# smoke_co_interface.net
KiCad netlist of a schematic drawn in EAGLE
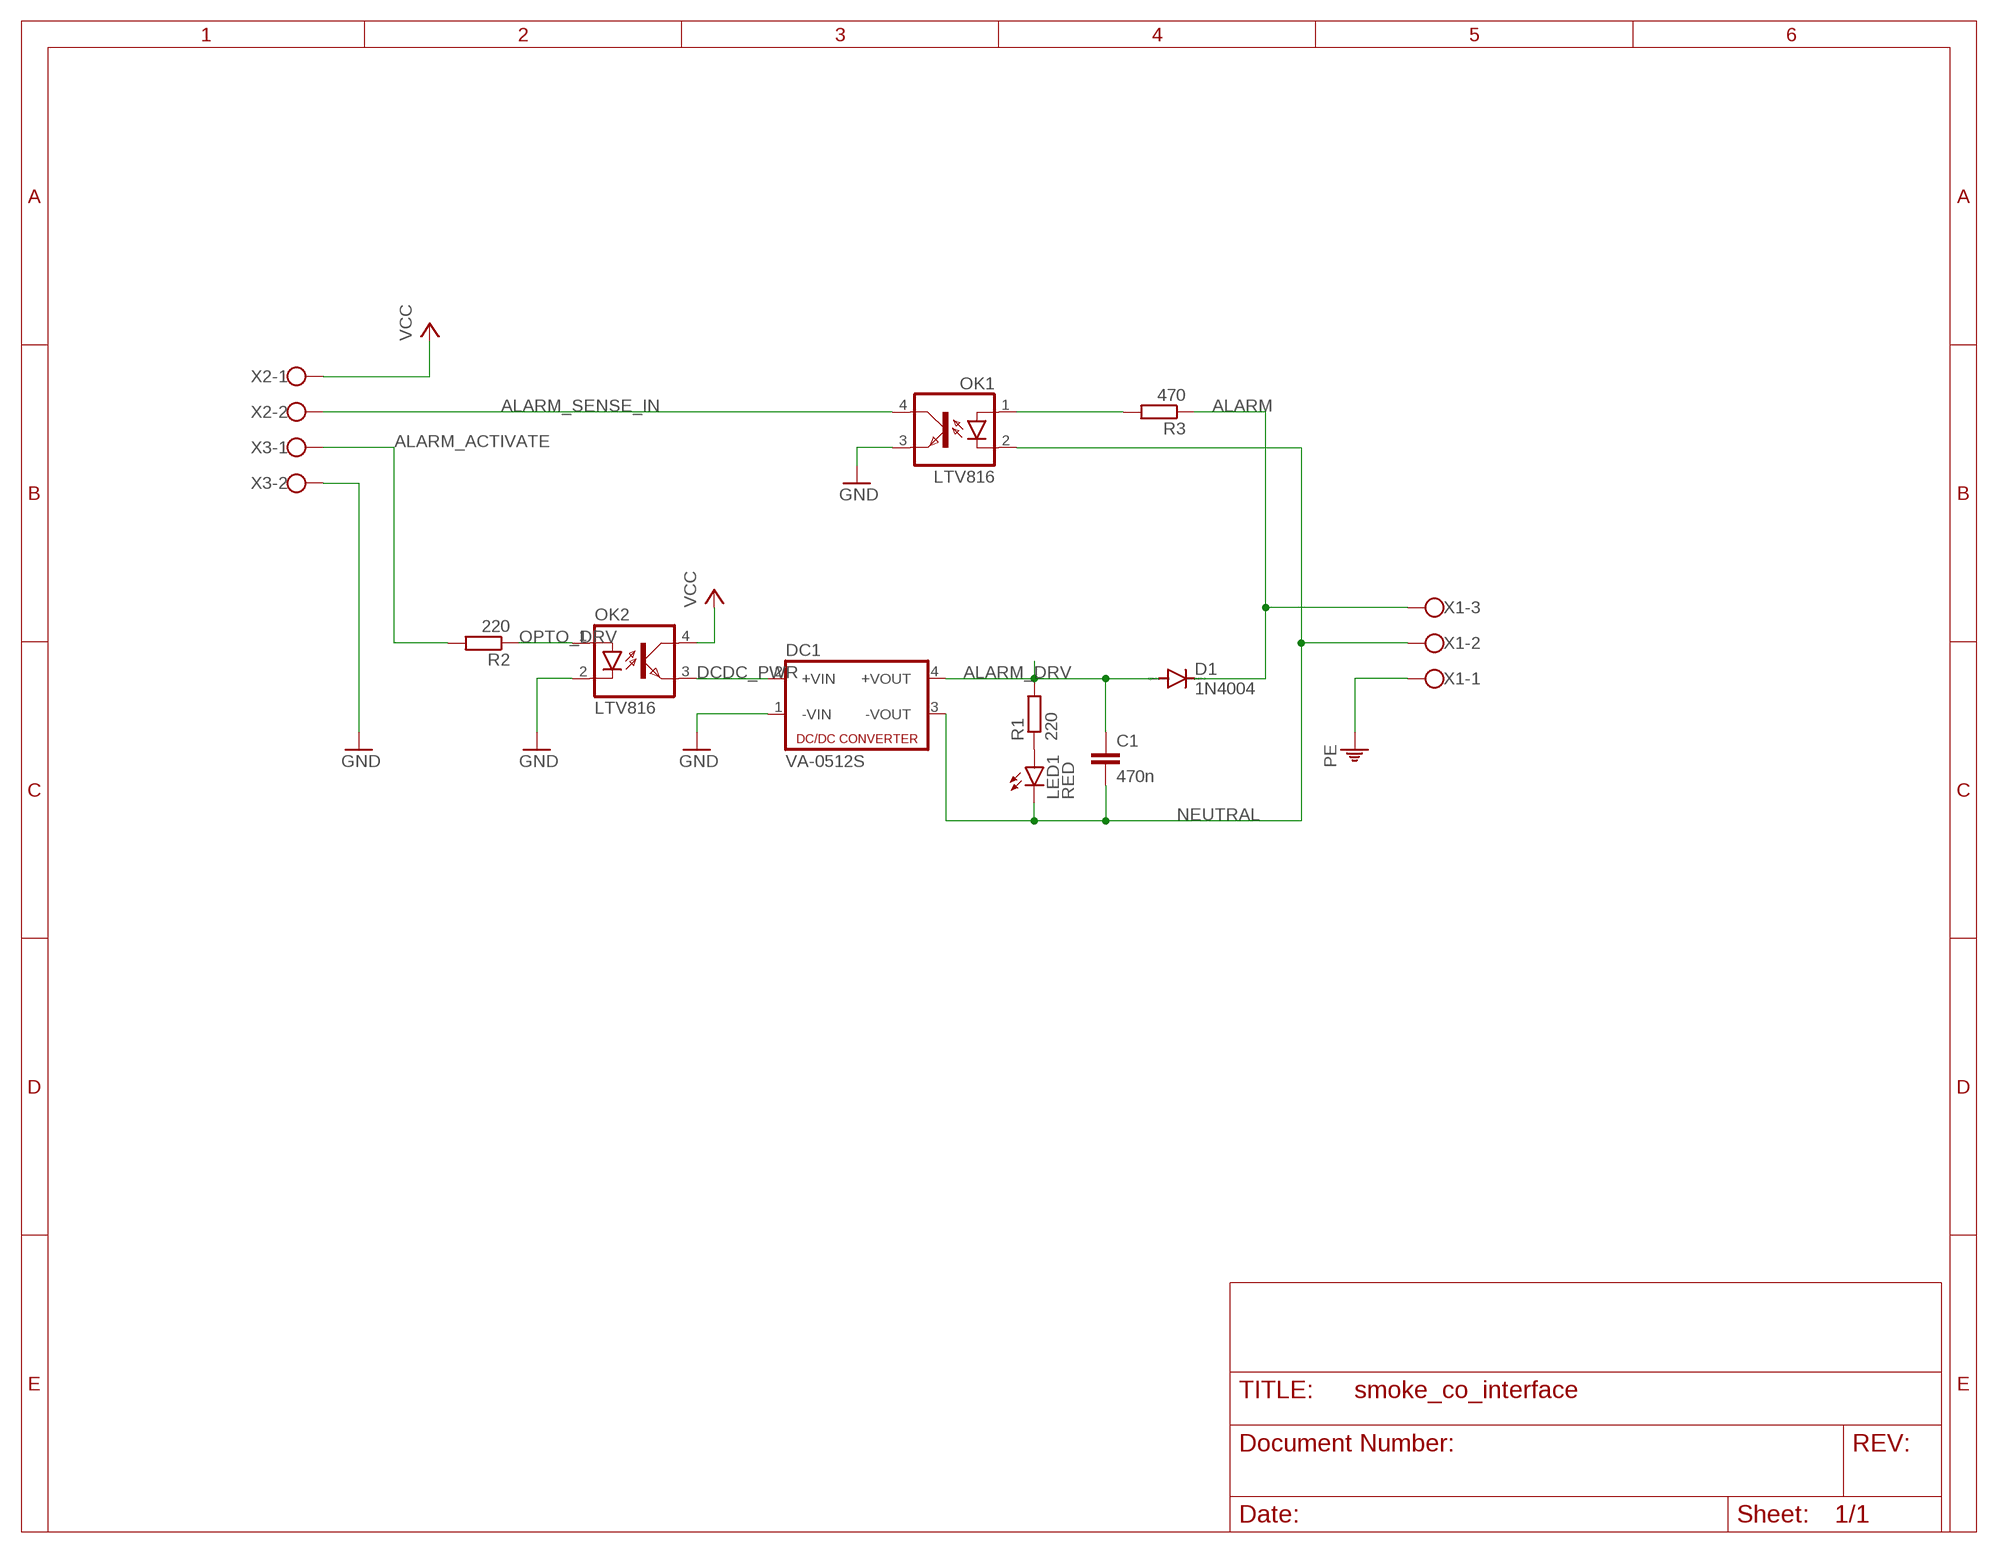
[diagram p0: schematic, sheet 1]

(export (version "E")
  (design (tool "Eeschema 10.0.6"))
  (components
    (comp (ref "C1")
      (value "470n")
      (footprint "eagle-import:C050-035X075")
      (libsource (lib "eagle-import") (part "C-EU050-035X075"))
    )
    (comp (ref "D1")
      (value "1N4004")
      (footprint "eagle-import:DO41-10")
      (libsource (lib "eagle-import") (part "1N4004"))
    )
    (comp (ref "DC1")
      (value "VA-0512S")
      (footprint "eagle-import:4SIL")
      (libsource (lib "eagle-import") (part "VA-?S0512"))
    )
    (comp (ref "LED1")
      (value "RED")
      (footprint "eagle-import:LED3MM")
      (libsource (lib "eagle-import") (part "LED3MM"))
    )
    (comp (ref "OK1")
      (value "LTV816")
      (footprint "eagle-import:DIL04")
      (libsource (lib "eagle-import") (part "LTV816"))
    )
    (comp (ref "OK2")
      (value "LTV816")
      (footprint "eagle-import:DIL04")
      (libsource (lib "eagle-import") (part "LTV816"))
    )
    (comp (ref "R1")
      (value "220")
      (footprint "eagle-import:0207_10")
      (libsource (lib "eagle-import") (part "R-EU_0207/10"))
    )
    (comp (ref "R2")
      (value "220")
      (footprint "eagle-import:0207_10")
      (libsource (lib "eagle-import") (part "R-EU_0207/10"))
    )
    (comp (ref "R3")
      (value "470")
      (footprint "eagle-import:0207_10")
      (libsource (lib "eagle-import") (part "R-EU_0207/10"))
    )
    (comp (ref "X1")
      (value "W237-103")
      (footprint "eagle-import:W237-103")
      (fields (field (name "MPN") "237-103"))
      (libsource (lib "eagle-import") (part "W237-103"))
    )
    (comp (ref "X2")
      (value "W237-102")
      (footprint "eagle-import:W237-102")
      (fields (field (name "MPN") "237-102"))
      (libsource (lib "eagle-import") (part "W237-102"))
    )
    (comp (ref "X3")
      (value "W237-102")
      (footprint "eagle-import:W237-102")
      (fields (field (name "MPN") "237-102"))
      (libsource (lib "eagle-import") (part "W237-102"))
    )
  )
  (nets
    (net (code "1") (name "/ALARM") (class "Default")
      (node (ref "D1") (pin "C") (pinfunction "C_C") (pintype "passive"))
      (node (ref "R3") (pin "1") (pinfunction "1_1") (pintype "passive"))
      (node (ref "X1") (pin "3") (pinfunction "KL_3") (pintype "passive"))
    )
    (net (code "2") (name "/ALARM_ACTIVATE") (class "Default")
      (node (ref "R2") (pin "2") (pinfunction "2_2") (pintype "passive"))
      (node (ref "X3") (pin "1") (pinfunction "KL_1") (pintype "passive"))
    )
    (net (code "3") (name "/ALARM_DRV") (class "Default")
      (node (ref "C1") (pin "1") (pinfunction "1_1") (pintype "passive"))
      (node (ref "D1") (pin "A") (pinfunction "A_A") (pintype "passive"))
      (node (ref "DC1") (pin "4") (pinfunction "+VOUT_4") (pintype "passive"))
      (node (ref "R1") (pin "2") (pinfunction "2_2") (pintype "passive"))
    )
    (net (code "4") (name "/ALARM_SENSE_IN") (class "Default")
      (node (ref "OK1") (pin "4") (pinfunction "COL_4") (pintype "passive"))
      (node (ref "X2") (pin "2") (pinfunction "KL_2") (pintype "passive"))
    )
    (net (code "5") (name "/DCDC_PWR") (class "Default")
      (node (ref "DC1") (pin "2") (pinfunction "+VIN_2") (pintype "passive"))
      (node (ref "OK2") (pin "3") (pinfunction "EMIT_3") (pintype "passive"))
    )
    (net (code "6") (name "/NEUTRAL") (class "Default")
      (node (ref "C1") (pin "2") (pinfunction "2_2") (pintype "passive"))
      (node (ref "DC1") (pin "3") (pinfunction "-VOUT_3") (pintype "passive"))
      (node (ref "LED1") (pin "K") (pinfunction "C_K") (pintype "passive"))
      (node (ref "OK1") (pin "2") (pinfunction "C_2") (pintype "passive"))
      (node (ref "X1") (pin "2") (pinfunction "KL_2") (pintype "passive"))
    )
    (net (code "7") (name "/OPTO_DRV") (class "Default")
      (node (ref "OK2") (pin "1") (pinfunction "A_1") (pintype "passive"))
      (node (ref "R2") (pin "1") (pinfunction "1_1") (pintype "passive"))
    )
    (net (code "8") (name "GND") (class "Default")
      (node (ref "DC1") (pin "1") (pinfunction "-VIN_1") (pintype "passive"))
      (node (ref "OK1") (pin "3") (pinfunction "EMIT_3") (pintype "passive"))
      (node (ref "OK2") (pin "2") (pinfunction "C_2") (pintype "passive"))
      (node (ref "X3") (pin "2") (pinfunction "KL_2") (pintype "passive"))
    )
    (net (code "9") (name "Net-(LED1-PadA)") (class "Default")
      (node (ref "LED1") (pin "A") (pinfunction "A_A") (pintype "passive"))
      (node (ref "R1") (pin "1") (pinfunction "1_1") (pintype "passive"))
    )
    (net (code "10") (name "Net-(OK1-A)") (class "Default")
      (node (ref "OK1") (pin "1") (pinfunction "A_1") (pintype "passive"))
      (node (ref "R3") (pin "2") (pinfunction "2_2") (pintype "passive"))
    )
    (net (code "11") (name "PE") (class "Default")
      (node (ref "X1") (pin "1") (pinfunction "KL_1") (pintype "passive"))
    )
    (net (code "12") (name "VCC") (class "Default")
      (node (ref "OK2") (pin "4") (pinfunction "COL_4") (pintype "passive"))
      (node (ref "X2") (pin "1") (pinfunction "KL_1") (pintype "passive"))
    )
  )
)
